# LB_BIT_w21_SUM-v03_1_0x.net
KiCad netlist of a schematic drawn in EAGLE
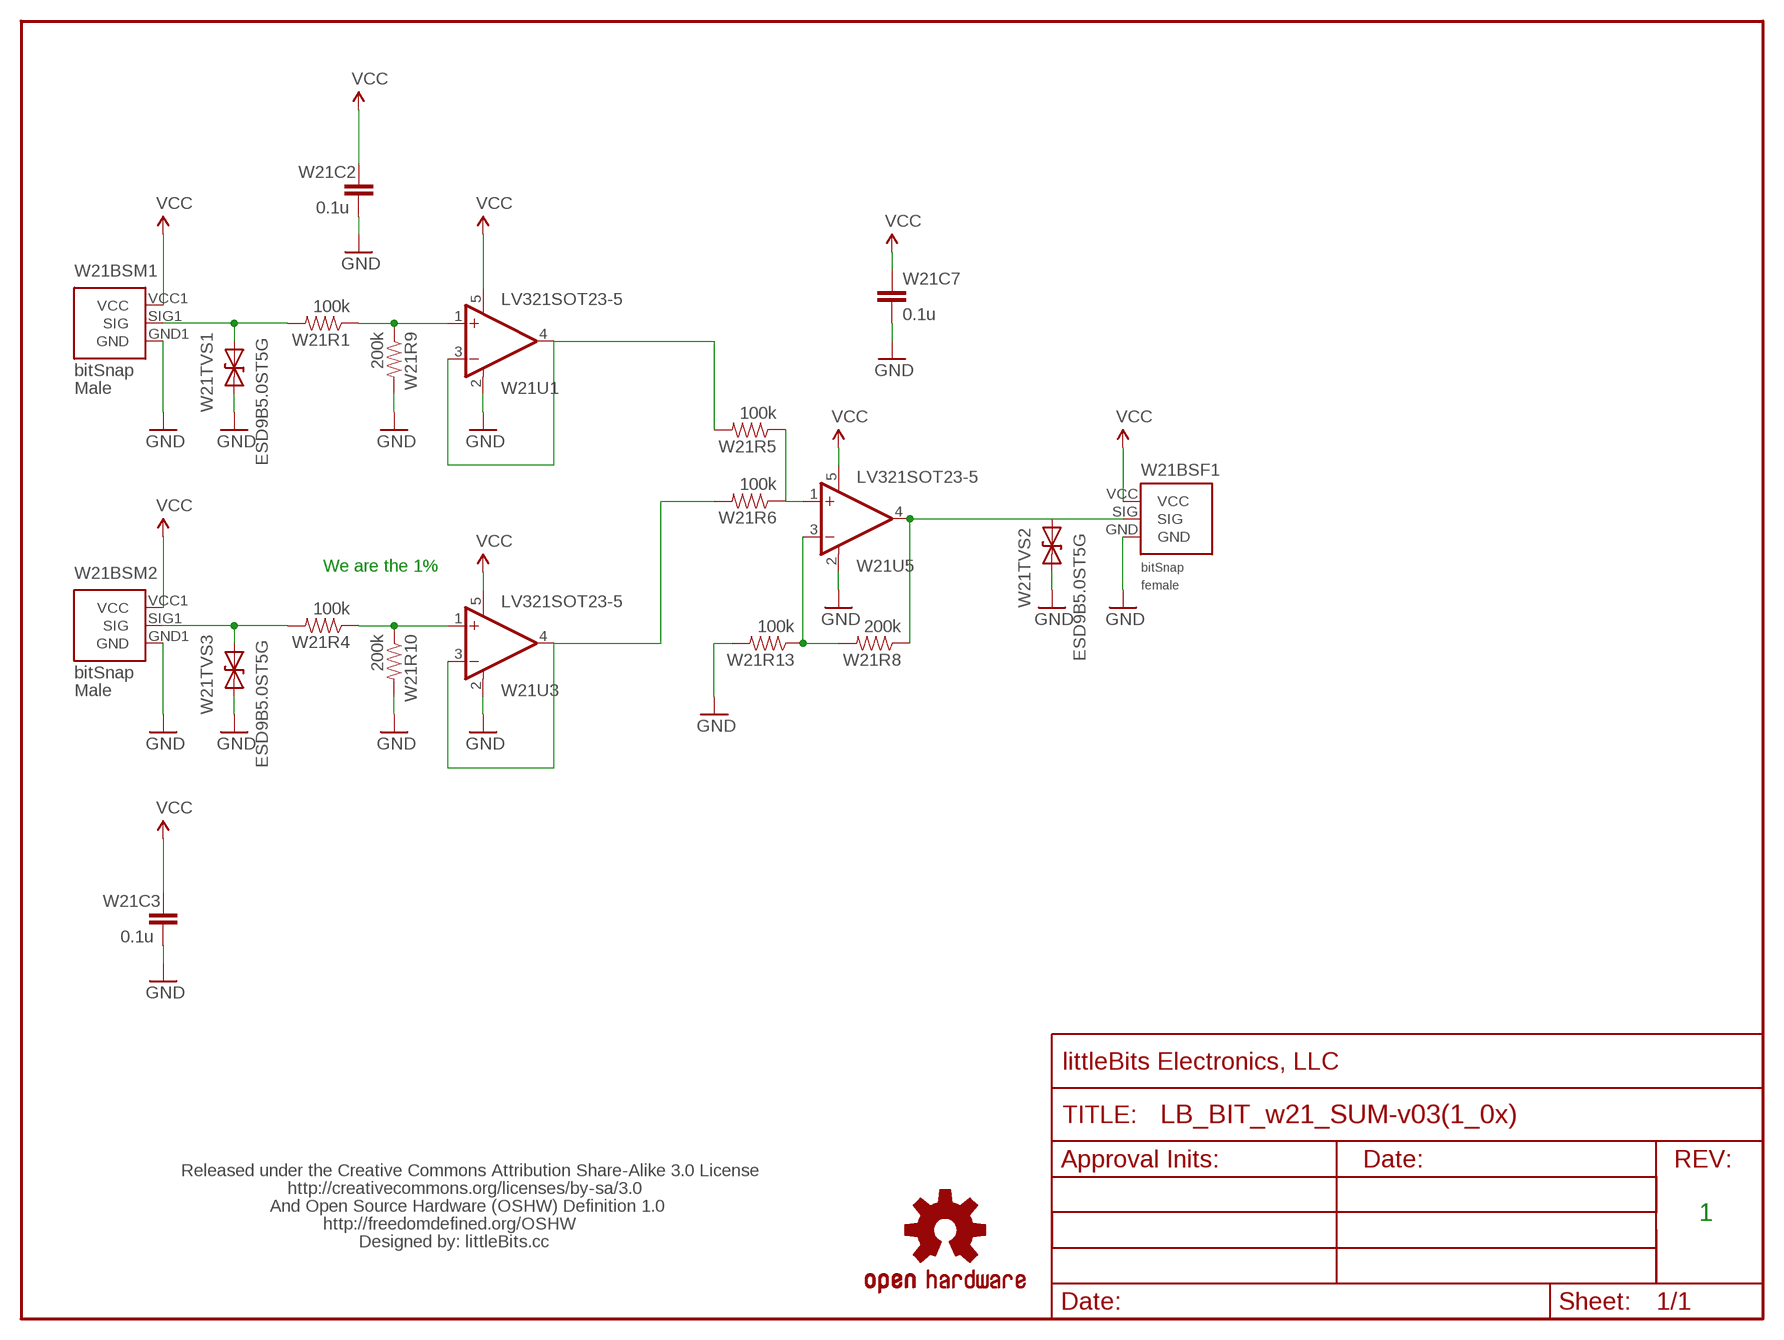
[diagram p0: schematic, sheet 1]

(export (version "E")
  (design (tool "Eeschema 10.0.6"))
  (components
    (comp (ref "FRAME1")
      (value "FRAME-LETTER")
      (footprint "eagle-import:FABDWG01")
      (libsource (lib "eagle-import") (part "FRAME-LETTER"))
    )
    (comp (ref "U$1")
      (value "OSHWCREDIT")
      (footprint "eagle-import:OSHWCREDIT")
      (libsource (lib "eagle-import") (part "OSHWCREDIT"))
    )
    (comp (ref "U$2")
      (value "OSHW-LOGOL")
      (footprint "eagle-import:OSHW-LOGO-L")
      (libsource (lib "eagle-import") (part "OSHW-LOGOL"))
    )
    (comp (ref "W21BSF1")
      (value "BITSNAP_V03_FEMALE")
      (footprint "eagle-import:BITSNAP_V03_FEMALE")
      (libsource (lib "eagle-import") (part "BITSNAP_V03_FEMALE"))
    )
    (comp (ref "W21BSM1")
      (value "BITSNAP_V03_MALE")
      (footprint "eagle-import:BITSNAP_V03_MALE")
      (libsource (lib "eagle-import") (part "BITSNAP_V03_MALE"))
    )
    (comp (ref "W21BSM2")
      (value "BITSNAP_V03_MALE")
      (footprint "eagle-import:BITSNAP_V03_MALE")
      (libsource (lib "eagle-import") (part "BITSNAP_V03_MALE"))
    )
    (comp (ref "W21C2")
      (value "0.1u")
      (footprint "eagle-import:CAP-0603")
      (libsource (lib "eagle-import") (part "CAPCAP-0603"))
    )
    (comp (ref "W21C3")
      (value "0.1u")
      (footprint "eagle-import:CAP-0603")
      (libsource (lib "eagle-import") (part "CAPCAP-0603"))
    )
    (comp (ref "W21C7")
      (value "0.1u")
      (footprint "eagle-import:CAP-0603")
      (libsource (lib "eagle-import") (part "CAPCAP-0603"))
    )
    (comp (ref "W21R1")
      (value "100k")
      (footprint "eagle-import:RES-0603")
      (libsource (lib "eagle-import") (part "RESISTOR0603"))
    )
    (comp (ref "W21R4")
      (value "100k")
      (footprint "eagle-import:RES-0603")
      (libsource (lib "eagle-import") (part "RESISTOR0603"))
    )
    (comp (ref "W21R5")
      (value "100k")
      (footprint "eagle-import:RES-0603")
      (libsource (lib "eagle-import") (part "RESISTOR0603"))
    )
    (comp (ref "W21R6")
      (value "100k")
      (footprint "eagle-import:RES-0603")
      (libsource (lib "eagle-import") (part "RESISTOR0603"))
    )
    (comp (ref "W21R8")
      (value "200k")
      (footprint "eagle-import:RES-0603")
      (libsource (lib "eagle-import") (part "RESISTOR0603"))
    )
    (comp (ref "W21R9")
      (value "200k")
      (footprint "eagle-import:RES-0603")
      (libsource (lib "eagle-import") (part "RESISTOR0603"))
    )
    (comp (ref "W21R10")
      (value "200k")
      (footprint "eagle-import:RES-0603")
      (libsource (lib "eagle-import") (part "RESISTOR0603"))
    )
    (comp (ref "W21R13")
      (value "100k")
      (footprint "eagle-import:RES-0603")
      (libsource (lib "eagle-import") (part "RESISTOR0603"))
    )
    (comp (ref "W21TVS1")
      (value "ESD9B5.0ST5G")
      (footprint "eagle-import:SOD-923")
      (libsource (lib "eagle-import") (part "DIODE-TVSSOD-923"))
    )
    (comp (ref "W21TVS2")
      (value "ESD9B5.0ST5G")
      (footprint "eagle-import:SOD-923")
      (libsource (lib "eagle-import") (part "DIODE-TVSSOD-923"))
    )
    (comp (ref "W21TVS3")
      (value "ESD9B5.0ST5G")
      (footprint "eagle-import:SOD-923")
      (libsource (lib "eagle-import") (part "DIODE-TVSSOD-923"))
    )
    (comp (ref "W21U1")
      (value "LV321SOT23-5")
      (footprint "eagle-import:SOT23-5")
      (libsource (lib "eagle-import") (part "LV321SOT23-5"))
    )
    (comp (ref "W21U3")
      (value "LV321SOT23-5")
      (footprint "eagle-import:SOT23-5")
      (libsource (lib "eagle-import") (part "LV321SOT23-5"))
    )
    (comp (ref "W21U5")
      (value "LV321SOT23-5")
      (footprint "eagle-import:SOT23-5")
      (libsource (lib "eagle-import") (part "LV321SOT23-5"))
    )
  )
  (nets
    (net (code "1") (name "GND") (class "Default")
      (node (ref "W21BSF1") (pin "GND") (pinfunction "GND_GND") (pintype "bidirectional"))
      (node (ref "W21BSM1") (pin "GND1") (pinfunction "GND_GND1") (pintype "bidirectional"))
      (node (ref "W21BSM2") (pin "GND1") (pinfunction "GND_GND1") (pintype "bidirectional"))
      (node (ref "W21C2") (pin "2") (pinfunction "2_2") (pintype "passive"))
      (node (ref "W21C3") (pin "2") (pinfunction "2_2") (pintype "passive"))
      (node (ref "W21C7") (pin "2") (pinfunction "2_2") (pintype "passive"))
      (node (ref "W21R10") (pin "2") (pinfunction "2_2") (pintype "passive"))
      (node (ref "W21R13") (pin "2") (pinfunction "2_2") (pintype "passive"))
      (node (ref "W21R9") (pin "2") (pinfunction "2_2") (pintype "passive"))
      (node (ref "W21TVS1") (pin "1") (pinfunction "A_1") (pintype "passive"))
      (node (ref "W21TVS2") (pin "1") (pinfunction "A_1") (pintype "passive"))
      (node (ref "W21TVS3") (pin "1") (pinfunction "A_1") (pintype "passive"))
      (node (ref "W21U1") (pin "2") (pinfunction "V-_2") (pintype "power_in"))
      (node (ref "W21U3") (pin "2") (pinfunction "V-_2") (pintype "power_in"))
      (node (ref "W21U5") (pin "2") (pinfunction "V-_2") (pintype "power_in"))
    )
    (net (code "2") (name "Net-(W21BSM1-SIG)") (class "Default")
      (node (ref "W21BSM1") (pin "SIG1") (pinfunction "SIG_SIG1") (pintype "bidirectional"))
      (node (ref "W21R1") (pin "2") (pinfunction "2_2") (pintype "passive"))
      (node (ref "W21TVS1") (pin "2") (pinfunction "C_2") (pintype "passive"))
    )
    (net (code "3") (name "Net-(W21BSM2-SIG)") (class "Default")
      (node (ref "W21BSM2") (pin "SIG1") (pinfunction "SIG_SIG1") (pintype "bidirectional"))
      (node (ref "W21R4") (pin "2") (pinfunction "2_2") (pintype "passive"))
      (node (ref "W21TVS3") (pin "2") (pinfunction "C_2") (pintype "passive"))
    )
    (net (code "4") (name "Net-(W21TVS2-C)") (class "Default")
      (node (ref "W21BSF1") (pin "SIG") (pinfunction "SIG_SIG") (pintype "bidirectional"))
      (node (ref "W21R8") (pin "1") (pinfunction "1_1") (pintype "passive"))
      (node (ref "W21TVS2") (pin "2") (pinfunction "C_2") (pintype "passive"))
      (node (ref "W21U5") (pin "4") (pinfunction "OUT_4") (pintype "output"))
    )
    (net (code "5") (name "Net-(W21U1-+IN)") (class "Default")
      (node (ref "W21R1") (pin "1") (pinfunction "1_1") (pintype "passive"))
      (node (ref "W21R9") (pin "1") (pinfunction "1_1") (pintype "passive"))
      (node (ref "W21U1") (pin "1") (pinfunction "+IN_1") (pintype "input"))
    )
    (net (code "6") (name "Net-(W21U1--IN)") (class "Default")
      (node (ref "W21R5") (pin "2") (pinfunction "2_2") (pintype "passive"))
      (node (ref "W21U1") (pin "3") (pinfunction "-IN_3") (pintype "input"))
      (node (ref "W21U1") (pin "4") (pinfunction "OUT_4") (pintype "output"))
    )
    (net (code "7") (name "Net-(W21U3-+IN)") (class "Default")
      (node (ref "W21R10") (pin "1") (pinfunction "1_1") (pintype "passive"))
      (node (ref "W21R4") (pin "1") (pinfunction "1_1") (pintype "passive"))
      (node (ref "W21U3") (pin "1") (pinfunction "+IN_1") (pintype "input"))
    )
    (net (code "8") (name "Net-(W21U3--IN)") (class "Default")
      (node (ref "W21R6") (pin "2") (pinfunction "2_2") (pintype "passive"))
      (node (ref "W21U3") (pin "3") (pinfunction "-IN_3") (pintype "input"))
      (node (ref "W21U3") (pin "4") (pinfunction "OUT_4") (pintype "output"))
    )
    (net (code "9") (name "Net-(W21U5-+IN)") (class "Default")
      (node (ref "W21R5") (pin "1") (pinfunction "1_1") (pintype "passive"))
      (node (ref "W21R6") (pin "1") (pinfunction "1_1") (pintype "passive"))
      (node (ref "W21U5") (pin "1") (pinfunction "+IN_1") (pintype "input"))
    )
    (net (code "10") (name "Net-(W21U5--IN)") (class "Default")
      (node (ref "W21R13") (pin "1") (pinfunction "1_1") (pintype "passive"))
      (node (ref "W21R8") (pin "2") (pinfunction "2_2") (pintype "passive"))
      (node (ref "W21U5") (pin "3") (pinfunction "-IN_3") (pintype "input"))
    )
    (net (code "11") (name "VCC") (class "Default")
      (node (ref "W21BSF1") (pin "VCC") (pinfunction "VCC_VCC") (pintype "bidirectional"))
      (node (ref "W21BSM1") (pin "VCC1") (pinfunction "VCC_VCC1") (pintype "bidirectional"))
      (node (ref "W21BSM2") (pin "VCC1") (pinfunction "VCC_VCC1") (pintype "bidirectional"))
      (node (ref "W21C2") (pin "1") (pinfunction "1_1") (pintype "passive"))
      (node (ref "W21C3") (pin "1") (pinfunction "1_1") (pintype "passive"))
      (node (ref "W21C7") (pin "1") (pinfunction "1_1") (pintype "passive"))
      (node (ref "W21U1") (pin "5") (pinfunction "V+_5") (pintype "power_in"))
      (node (ref "W21U3") (pin "5") (pinfunction "V+_5") (pintype "power_in"))
      (node (ref "W21U5") (pin "5") (pinfunction "V+_5") (pintype "power_in"))
    )
  )
)
